# ServoBoard.net
KiCad netlist of a schematic drawn in Altium Designer
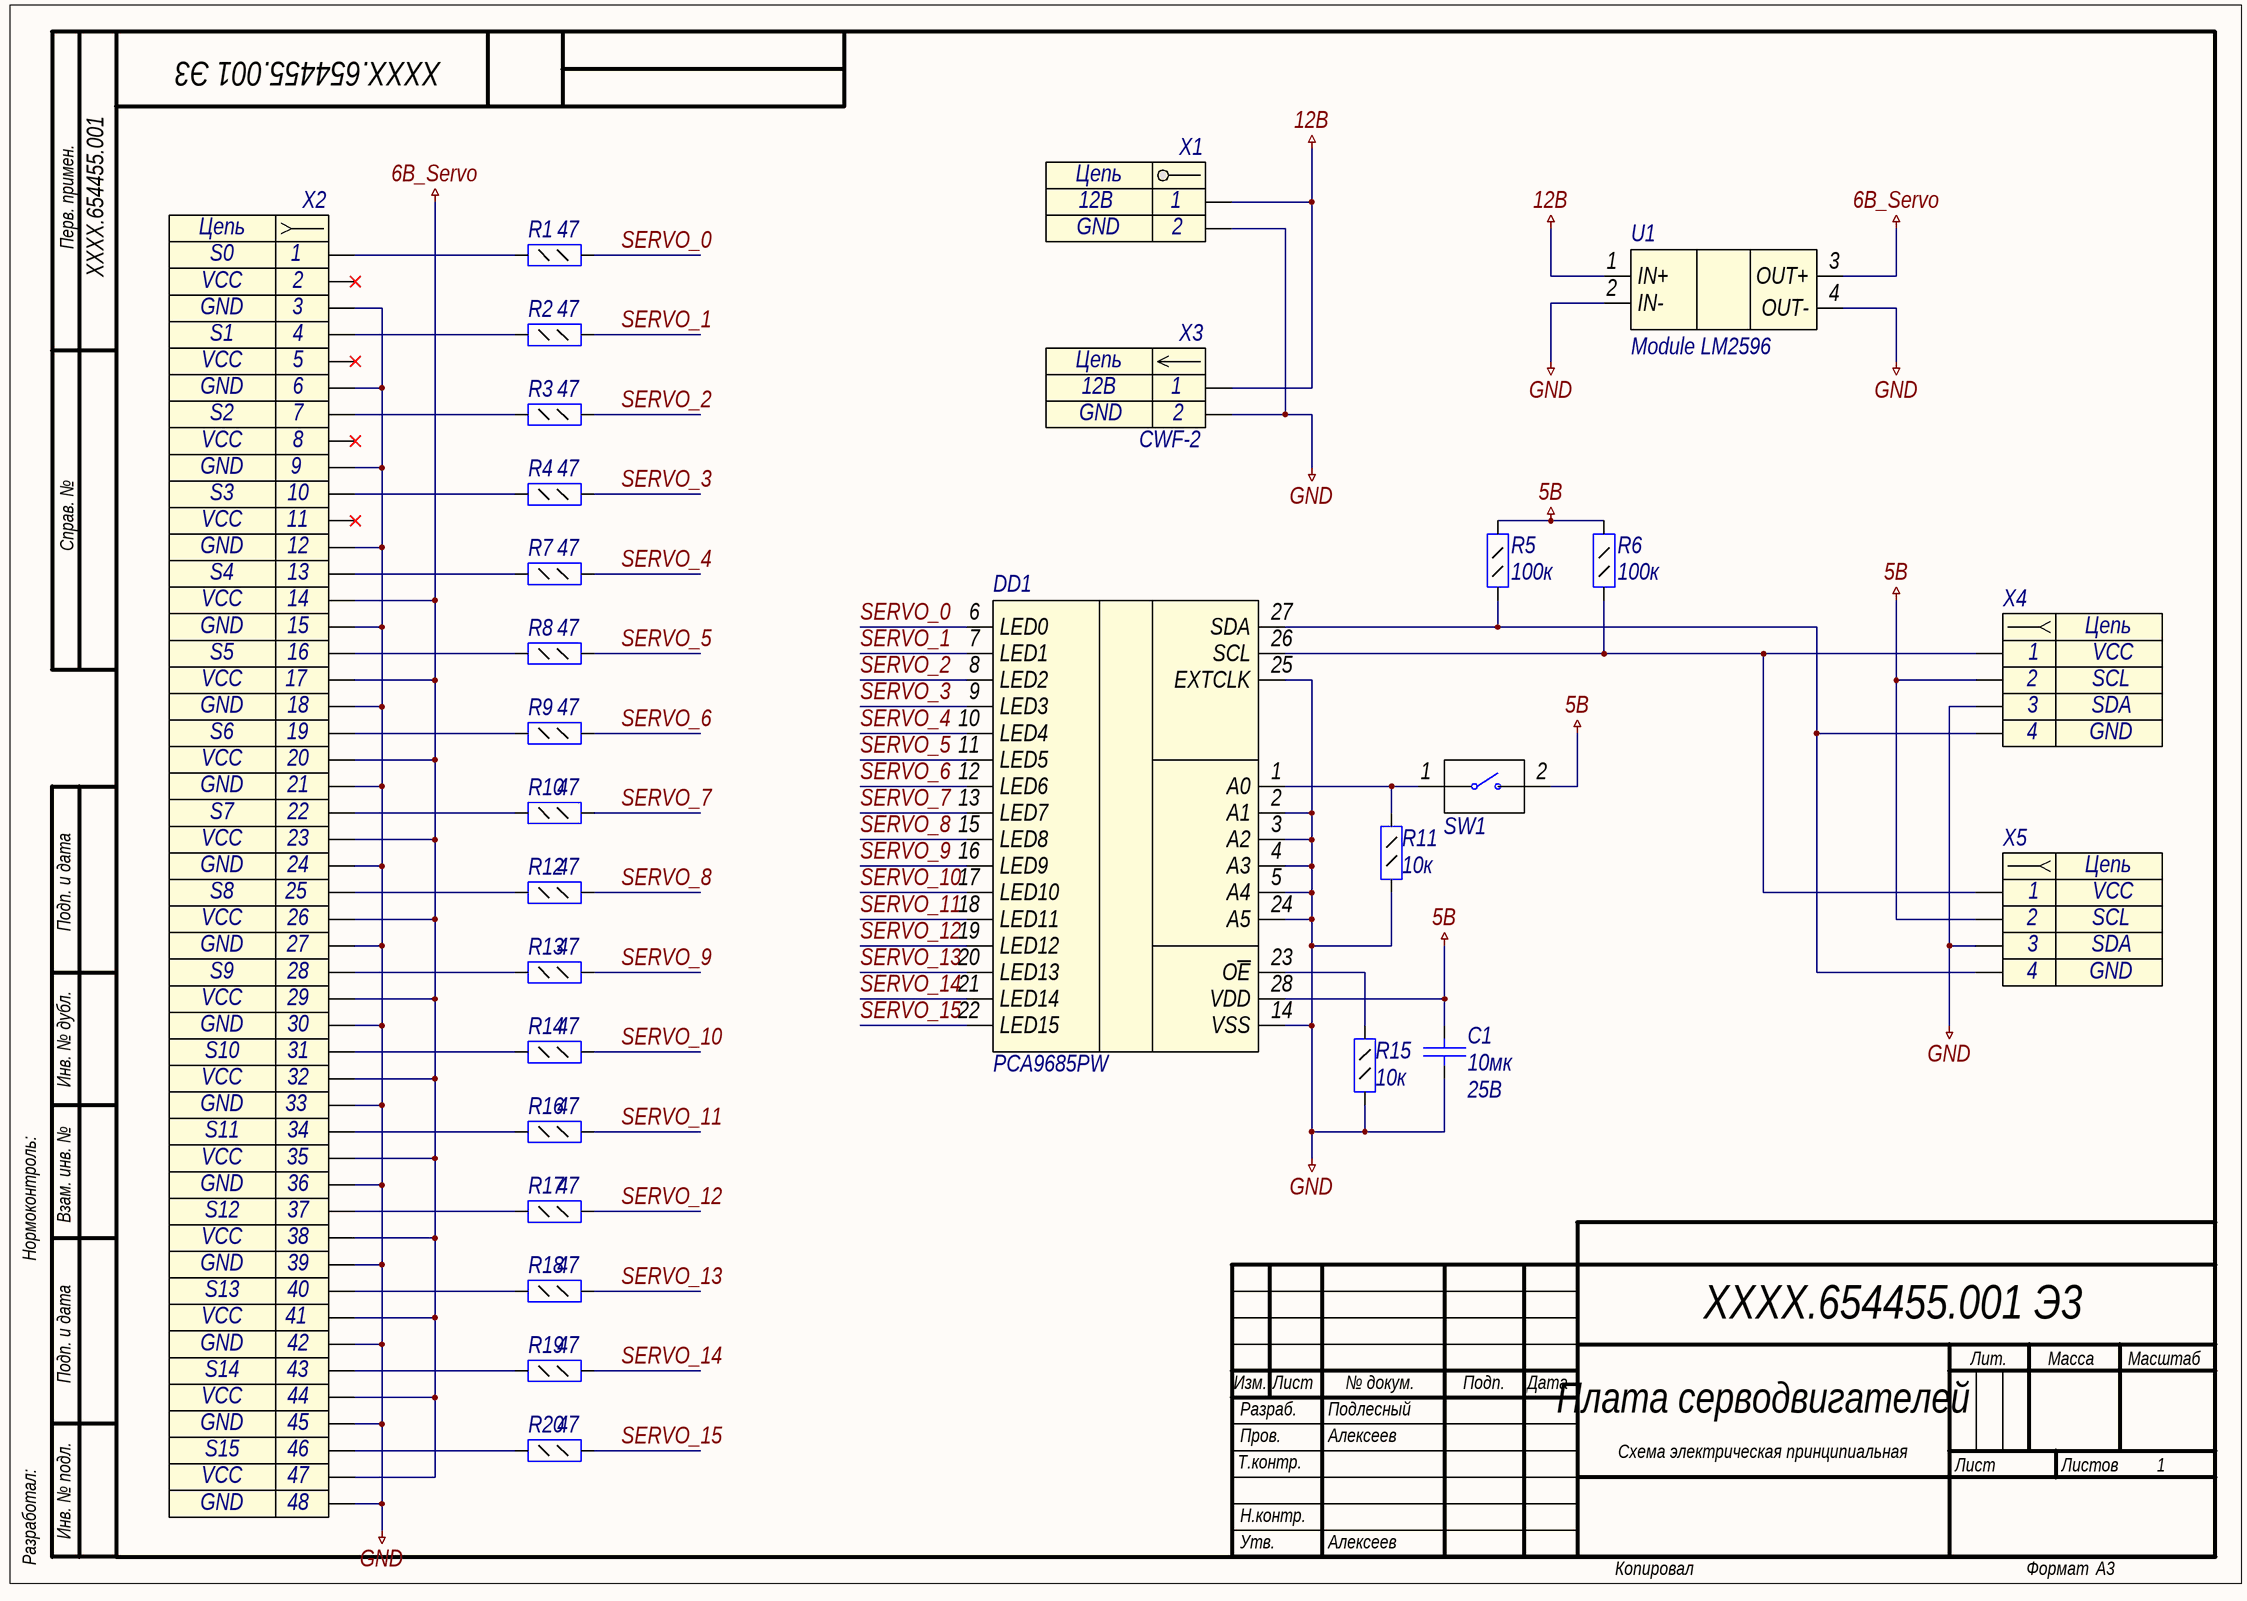
[diagram p0: ServoBoard.schdoc]

(export (version "E")
  (design (tool "Eeschema 10.0.6"))
  (components
    (comp (ref "C1")
      (value "10мк")
      (footprint "C1206")
      (description "Конденсатор")
      (fields
        (field (name "VOLTAGE") "25В")
        (field (name "PART NUMBER") "GRM31CR71E106KA12L*")
        (field (name "Comment") "Capacitor")
      )
      (libsource (lib "MOP44") (part "Capacitor"))
    )
    (comp (ref "DD1")
      (value "PCA9685PW")
      (footprint "TSSOP28")
      (description "Драйвер светодиода, 16 выходов")
      (fields (field (name "PART NUMBER") "PCA9685PW,112"))
      (libsource (lib "MOP44") (part "PCA9685PW"))
    )
    (comp (ref "R1")
      (value "47")
      (footprint "R0805")
      (description "Резистор")
      (fields (field (name "PART NUMBER") "RC0805FR-0747RL") (field (name "POWER") "0,125Вт"))
      (libsource (lib "MOP44") (part "Resistor_0,125Вт"))
    )
    (comp (ref "R2")
      (value "47")
      (footprint "R0805")
      (description "Резистор")
      (fields (field (name "PART NUMBER") "RC0805FR-0747RL") (field (name "POWER") "0,125Вт"))
      (libsource (lib "MOP44") (part "Resistor_0,125Вт"))
    )
    (comp (ref "R3")
      (value "47")
      (footprint "R0805")
      (description "Резистор")
      (fields (field (name "PART NUMBER") "RC0805FR-0747RL") (field (name "POWER") "0,125Вт"))
      (libsource (lib "MOP44") (part "Resistor_0,125Вт"))
    )
    (comp (ref "R4")
      (value "47")
      (footprint "R0805")
      (description "Резистор")
      (fields (field (name "PART NUMBER") "RC0805FR-0747RL") (field (name "POWER") "0,125Вт"))
      (libsource (lib "MOP44") (part "Resistor_0,125Вт"))
    )
    (comp (ref "R5")
      (value "100к")
      (footprint "R0805")
      (description "Резистор")
      (fields (field (name "PART NUMBER") "RC0805FR-07100KL") (field (name "POWER") "0,125Вт"))
      (libsource (lib "") (part "Resistor_0,125Вт_1"))
    )
    (comp (ref "R6")
      (value "100к")
      (footprint "R0805")
      (description "Резистор")
      (fields (field (name "PART NUMBER") "RC0805FR-07100KL") (field (name "POWER") "0,125Вт"))
      (libsource (lib "") (part "Resistor_0,125Вт_1"))
    )
    (comp (ref "R7")
      (value "47")
      (footprint "R0805")
      (description "Резистор")
      (fields (field (name "PART NUMBER") "RC0805FR-0747RL") (field (name "POWER") "0,125Вт"))
      (libsource (lib "MOP44") (part "Resistor_0,125Вт"))
    )
    (comp (ref "R8")
      (value "47")
      (footprint "R0805")
      (description "Резистор")
      (fields (field (name "PART NUMBER") "RC0805FR-0747RL") (field (name "POWER") "0,125Вт"))
      (libsource (lib "MOP44") (part "Resistor_0,125Вт"))
    )
    (comp (ref "R9")
      (value "47")
      (footprint "R0805")
      (description "Резистор")
      (fields (field (name "PART NUMBER") "RC0805FR-0747RL") (field (name "POWER") "0,125Вт"))
      (libsource (lib "MOP44") (part "Resistor_0,125Вт"))
    )
    (comp (ref "R10")
      (value "47")
      (footprint "R0805")
      (description "Резистор")
      (fields (field (name "PART NUMBER") "RC0805FR-0747RL") (field (name "POWER") "0,125Вт"))
      (libsource (lib "MOP44") (part "Resistor_0,125Вт"))
    )
    (comp (ref "R11")
      (value "10к")
      (footprint "R0805")
      (description "Резистор")
      (fields (field (name "POWER") "0,125Вт") (field (name "Comment") "Resistor_0,125Вт"))
      (libsource (lib "") (part "Resistor_0,125Вт_2"))
    )
    (comp (ref "R12")
      (value "47")
      (footprint "R0805")
      (description "Резистор")
      (fields (field (name "PART NUMBER") "RC0805FR-0747RL") (field (name "POWER") "0,125Вт"))
      (libsource (lib "MOP44") (part "Resistor_0,125Вт"))
    )
    (comp (ref "R13")
      (value "47")
      (footprint "R0805")
      (description "Резистор")
      (fields (field (name "PART NUMBER") "RC0805FR-0747RL") (field (name "POWER") "0,125Вт"))
      (libsource (lib "MOP44") (part "Resistor_0,125Вт"))
    )
    (comp (ref "R14")
      (value "47")
      (footprint "R0805")
      (description "Резистор")
      (fields (field (name "PART NUMBER") "RC0805FR-0747RL") (field (name "POWER") "0,125Вт"))
      (libsource (lib "MOP44") (part "Resistor_0,125Вт"))
    )
    (comp (ref "R15")
      (value "10к")
      (footprint "R0805")
      (description "Резистор")
      (fields (field (name "POWER") "0,125Вт") (field (name "Comment") "Resistor_0,125Вт"))
      (libsource (lib "") (part "Resistor_0,125Вт_2"))
    )
    (comp (ref "R16")
      (value "47")
      (footprint "R0805")
      (description "Резистор")
      (fields (field (name "PART NUMBER") "RC0805FR-0747RL") (field (name "POWER") "0,125Вт"))
      (libsource (lib "MOP44") (part "Resistor_0,125Вт"))
    )
    (comp (ref "R17")
      (value "47")
      (footprint "R0805")
      (description "Резистор")
      (fields (field (name "PART NUMBER") "RC0805FR-0747RL") (field (name "POWER") "0,125Вт"))
      (libsource (lib "MOP44") (part "Resistor_0,125Вт"))
    )
    (comp (ref "R18")
      (value "47")
      (footprint "R0805")
      (description "Резистор")
      (fields (field (name "PART NUMBER") "RC0805FR-0747RL") (field (name "POWER") "0,125Вт"))
      (libsource (lib "MOP44") (part "Resistor_0,125Вт"))
    )
    (comp (ref "R19")
      (value "47")
      (footprint "R0805")
      (description "Резистор")
      (fields (field (name "PART NUMBER") "RC0805FR-0747RL") (field (name "POWER") "0,125Вт"))
      (libsource (lib "MOP44") (part "Resistor_0,125Вт"))
    )
    (comp (ref "R20")
      (value "47")
      (footprint "R0805")
      (description "Резистор")
      (fields (field (name "PART NUMBER") "RC0805FR-0747RL") (field (name "POWER") "0,125Вт"))
      (libsource (lib "MOP44") (part "Resistor_0,125Вт"))
    )
    (comp (ref "SW1")
      (value "DS1040-01")
      (footprint "1PAD_ADR")
      (description "DIP переключатель")
      (libsource (lib "MOP44") (part "DS1040-01"))
    )
    (comp (ref "U1")
      (value "Module LM2596")
      (footprint "module LM2596")
      (description "Low-Dropout Regulator for 5-V to 3.3-V Conversion")
      (libsource (lib "MOP44") (part "Module LM2596"))
    )
    (comp (ref "X1")
      (value "Header_2_trm")
      (footprint "TERMINAL-2WAY-3.5MM")
      (description "Разъем - 2 конт. клеммник")
      (libsource (lib "MOP44") (part "Header_2_trm"))
    )
    (comp (ref "X2")
      (value "Header_48_plg")
      (footprint "PLS-48")
      (description "Разъем - 5 конт. вилка")
      (fields (field (name "PART NUMBER") "DS1021-1*48SF112-B"))
      (libsource (lib "MOP44") (part "Header_48_plg"))
    )
    (comp (ref "X3")
      (value "~")
      (footprint "CWF-2")
      (description "Разъем - 2 конт. вилка")
      (fields (field (name "PART NAME") "CWF-2") (field (name "PART NUMBER") "DS1069-2MVW6X"))
      (libsource (lib "MOP44") (part "Header_2_plg"))
    )
    (comp (ref "X4")
      (value "Header_4_sct")
      (footprint "RJ11_4P4C_V")
      (description "Разъем - 4 конт. розетка")
      (libsource (lib "MOP44") (part "Header_4_sct"))
    )
    (comp (ref "X5")
      (value "Header_4_sct")
      (footprint "RJ11_4P4C_V")
      (description "Разъем - 4 конт. розетка")
      (libsource (lib "MOP44") (part "Header_4_sct"))
    )
  )
  (nets
    (net (code "1") (name "/SERVO_0") (class "Default")
      (node (ref "DD1") (pin "6") (pinfunction "LED0_6") (pintype "power_in"))
      (node (ref "R1") (pin "2") (pinfunction "2_2") (pintype "passive"))
    )
    (net (code "2") (name "/SERVO_1") (class "Default")
      (node (ref "DD1") (pin "7") (pinfunction "LED1_7") (pintype "power_in"))
      (node (ref "R2") (pin "2") (pinfunction "2_2") (pintype "passive"))
    )
    (net (code "3") (name "/SERVO_2") (class "Default")
      (node (ref "DD1") (pin "8") (pinfunction "LED2_8") (pintype "power_in"))
      (node (ref "R3") (pin "2") (pinfunction "2_2") (pintype "passive"))
    )
    (net (code "4") (name "/SERVO_3") (class "Default")
      (node (ref "DD1") (pin "9") (pinfunction "LED3_9") (pintype "power_in"))
      (node (ref "R4") (pin "2") (pinfunction "2_2") (pintype "passive"))
    )
    (net (code "5") (name "/SERVO_4") (class "Default")
      (node (ref "DD1") (pin "10") (pinfunction "LED4_10") (pintype "power_in"))
      (node (ref "R7") (pin "2") (pinfunction "2_2") (pintype "passive"))
    )
    (net (code "6") (name "/SERVO_5") (class "Default")
      (node (ref "DD1") (pin "11") (pinfunction "LED5_11") (pintype "power_in"))
      (node (ref "R8") (pin "2") (pinfunction "2_2") (pintype "passive"))
    )
    (net (code "7") (name "/SERVO_6") (class "Default")
      (node (ref "DD1") (pin "12") (pinfunction "LED6_12") (pintype "power_in"))
      (node (ref "R9") (pin "2") (pinfunction "2_2") (pintype "passive"))
    )
    (net (code "8") (name "/SERVO_7") (class "Default")
      (node (ref "DD1") (pin "13") (pinfunction "LED7_13") (pintype "power_in"))
      (node (ref "R10") (pin "2") (pinfunction "2_2") (pintype "passive"))
    )
    (net (code "9") (name "/SERVO_8") (class "Default")
      (node (ref "DD1") (pin "15") (pinfunction "LED8_15") (pintype "power_in"))
      (node (ref "R12") (pin "2") (pinfunction "2_2") (pintype "passive"))
    )
    (net (code "10") (name "/SERVO_9") (class "Default")
      (node (ref "DD1") (pin "16") (pinfunction "LED9_16") (pintype "power_in"))
      (node (ref "R13") (pin "2") (pinfunction "2_2") (pintype "passive"))
    )
    (net (code "11") (name "/SERVO_10") (class "Default")
      (node (ref "DD1") (pin "17") (pinfunction "LED10_17") (pintype "power_in"))
      (node (ref "R14") (pin "2") (pinfunction "2_2") (pintype "passive"))
    )
    (net (code "12") (name "/SERVO_11") (class "Default")
      (node (ref "DD1") (pin "18") (pinfunction "LED11_18") (pintype "power_in"))
      (node (ref "R16") (pin "2") (pinfunction "2_2") (pintype "passive"))
    )
    (net (code "13") (name "/SERVO_12") (class "Default")
      (node (ref "DD1") (pin "19") (pinfunction "LED12_19") (pintype "power_in"))
      (node (ref "R17") (pin "2") (pinfunction "2_2") (pintype "passive"))
    )
    (net (code "14") (name "/SERVO_13") (class "Default")
      (node (ref "DD1") (pin "20") (pinfunction "LED13_20") (pintype "power_in"))
      (node (ref "R18") (pin "2") (pinfunction "2_2") (pintype "passive"))
    )
    (net (code "15") (name "/SERVO_14") (class "Default")
      (node (ref "DD1") (pin "21") (pinfunction "LED14_21") (pintype "power_in"))
      (node (ref "R19") (pin "2") (pinfunction "2_2") (pintype "passive"))
    )
    (net (code "16") (name "/SERVO_15") (class "Default")
      (node (ref "DD1") (pin "22") (pinfunction "LED15_22") (pintype "power_in"))
      (node (ref "R20") (pin "2") (pinfunction "2_2") (pintype "passive"))
    )
    (net (code "17") (name "5B") (class "Default")
      (node (ref "C1") (pin "2") (pinfunction "2_2") (pintype "passive"))
      (node (ref "DD1") (pin "28") (pinfunction "VDD_28") (pintype "power_in"))
      (node (ref "R5") (pin "2") (pinfunction "2_2") (pintype "passive"))
      (node (ref "R6") (pin "2") (pinfunction "2_2") (pintype "passive"))
      (node (ref "SW1") (pin "2") (pintype "passive"))
      (node (ref "X4") (pin "2") (pinfunction "2_2") (pintype "passive"))
      (node (ref "X5") (pin "2") (pinfunction "2_2") (pintype "passive"))
    )
    (net (code "18") (name "6B_Servo") (class "Default")
      (node (ref "U1") (pin "3") (pinfunction "OUT+_3") (pintype "power_in"))
      (node (ref "X2") (pin "14") (pinfunction "14_14") (pintype "passive"))
      (node (ref "X2") (pin "17") (pinfunction "17_17") (pintype "passive"))
      (node (ref "X2") (pin "20") (pinfunction "20_20") (pintype "passive"))
      (node (ref "X2") (pin "23") (pinfunction "23_23") (pintype "passive"))
      (node (ref "X2") (pin "26") (pinfunction "26_26") (pintype "passive"))
      (node (ref "X2") (pin "29") (pinfunction "29_29") (pintype "passive"))
      (node (ref "X2") (pin "32") (pinfunction "32_32") (pintype "passive"))
      (node (ref "X2") (pin "35") (pinfunction "35_35") (pintype "passive"))
      (node (ref "X2") (pin "38") (pinfunction "38_38") (pintype "passive"))
      (node (ref "X2") (pin "41") (pinfunction "41_41") (pintype "passive"))
      (node (ref "X2") (pin "44") (pinfunction "44_44") (pintype "passive"))
      (node (ref "X2") (pin "47") (pinfunction "47_47") (pintype "passive"))
    )
    (net (code "19") (name "12B") (class "Default")
      (node (ref "U1") (pin "1") (pinfunction "IN+_1") (pintype "power_in"))
      (node (ref "X1") (pin "1") (pinfunction "1_1") (pintype "passive"))
      (node (ref "X3") (pin "1") (pinfunction "1_1") (pintype "passive"))
    )
    (net (code "20") (name "GND") (class "Default")
      (node (ref "C1") (pin "1") (pinfunction "1_1") (pintype "passive"))
      (node (ref "DD1") (pin "14") (pinfunction "VSS_14") (pintype "power_in"))
      (node (ref "DD1") (pin "2") (pinfunction "A1_2") (pintype "power_in"))
      (node (ref "DD1") (pin "24") (pinfunction "A5_24") (pintype "power_in"))
      (node (ref "DD1") (pin "25") (pinfunction "EXTCLK_25") (pintype "power_in"))
      (node (ref "DD1") (pin "3") (pinfunction "A2_3") (pintype "power_in"))
      (node (ref "DD1") (pin "4") (pinfunction "A3_4") (pintype "power_in"))
      (node (ref "DD1") (pin "5") (pinfunction "A4_5") (pintype "power_in"))
      (node (ref "R11") (pin "2") (pinfunction "2_2") (pintype "passive"))
      (node (ref "R15") (pin "2") (pinfunction "2_2") (pintype "passive"))
      (node (ref "U1") (pin "2") (pinfunction "IN-_2") (pintype "power_in"))
      (node (ref "U1") (pin "4") (pinfunction "OUT-_4") (pintype "power_in"))
      (node (ref "X1") (pin "2") (pinfunction "2_2") (pintype "passive"))
      (node (ref "X2") (pin "12") (pinfunction "12_12") (pintype "passive"))
      (node (ref "X2") (pin "15") (pinfunction "15_15") (pintype "passive"))
      (node (ref "X2") (pin "18") (pinfunction "18_18") (pintype "passive"))
      (node (ref "X2") (pin "21") (pinfunction "21_21") (pintype "passive"))
      (node (ref "X2") (pin "24") (pinfunction "24_24") (pintype "passive"))
      (node (ref "X2") (pin "27") (pinfunction "27_27") (pintype "passive"))
      (node (ref "X2") (pin "3") (pinfunction "3_3") (pintype "passive"))
      (node (ref "X2") (pin "30") (pinfunction "30_30") (pintype "passive"))
      (node (ref "X2") (pin "33") (pinfunction "33_33") (pintype "passive"))
      (node (ref "X2") (pin "36") (pinfunction "36_36") (pintype "passive"))
      (node (ref "X2") (pin "39") (pinfunction "39_39") (pintype "passive"))
      (node (ref "X2") (pin "42") (pinfunction "42_42") (pintype "passive"))
      (node (ref "X2") (pin "45") (pinfunction "45_45") (pintype "passive"))
      (node (ref "X2") (pin "48") (pinfunction "48_48") (pintype "passive"))
      (node (ref "X2") (pin "6") (pinfunction "6_6") (pintype "passive"))
      (node (ref "X2") (pin "9") (pinfunction "9_9") (pintype "passive"))
      (node (ref "X3") (pin "2") (pinfunction "2_2") (pintype "passive"))
      (node (ref "X4") (pin "3") (pinfunction "3_3") (pintype "passive"))
      (node (ref "X5") (pin "3") (pinfunction "3_3") (pintype "passive"))
    )
    (net (code "21") (name "Net-(DD1-A0)") (class "Default")
      (node (ref "DD1") (pin "1") (pinfunction "A0_1") (pintype "power_in"))
      (node (ref "R11") (pin "1") (pinfunction "1_1") (pintype "passive"))
      (node (ref "SW1") (pin "1") (pintype "passive"))
    )
    (net (code "22") (name "Net-(DD1-O~{E})") (class "Default")
      (node (ref "DD1") (pin "23") (pinfunction "O~{E}_23") (pintype "power_in"))
      (node (ref "R15") (pin "1") (pinfunction "1_1") (pintype "passive"))
    )
    (net (code "23") (name "Net-(DD1-SCL)") (class "Default")
      (node (ref "DD1") (pin "26") (pinfunction "SCL_26") (pintype "power_in"))
      (node (ref "R6") (pin "1") (pinfunction "1_1") (pintype "passive"))
      (node (ref "X4") (pin "1") (pinfunction "1_1") (pintype "passive"))
      (node (ref "X5") (pin "1") (pinfunction "1_1") (pintype "passive"))
    )
    (net (code "24") (name "Net-(DD1-SDA)") (class "Default")
      (node (ref "DD1") (pin "27") (pinfunction "SDA_27") (pintype "power_in"))
      (node (ref "R5") (pin "1") (pinfunction "1_1") (pintype "passive"))
      (node (ref "X4") (pin "4") (pinfunction "4_4") (pintype "passive"))
      (node (ref "X5") (pin "4") (pinfunction "4_4") (pintype "passive"))
    )
    (net (code "25") (name "Net-(R1-Pad1)") (class "Default")
      (node (ref "R1") (pin "1") (pinfunction "1_1") (pintype "passive"))
      (node (ref "X2") (pin "1") (pinfunction "1_1") (pintype "passive"))
    )
    (net (code "26") (name "Net-(R2-Pad1)") (class "Default")
      (node (ref "R2") (pin "1") (pinfunction "1_1") (pintype "passive"))
      (node (ref "X2") (pin "4") (pinfunction "4_4") (pintype "passive"))
    )
    (net (code "27") (name "Net-(R3-Pad1)") (class "Default")
      (node (ref "R3") (pin "1") (pinfunction "1_1") (pintype "passive"))
      (node (ref "X2") (pin "7") (pinfunction "7_7") (pintype "passive"))
    )
    (net (code "28") (name "Net-(R4-Pad1)") (class "Default")
      (node (ref "R4") (pin "1") (pinfunction "1_1") (pintype "passive"))
      (node (ref "X2") (pin "10") (pinfunction "10_10") (pintype "passive"))
    )
    (net (code "29") (name "Net-(R7-Pad1)") (class "Default")
      (node (ref "R7") (pin "1") (pinfunction "1_1") (pintype "passive"))
      (node (ref "X2") (pin "13") (pinfunction "13_13") (pintype "passive"))
    )
    (net (code "30") (name "Net-(R8-Pad1)") (class "Default")
      (node (ref "R8") (pin "1") (pinfunction "1_1") (pintype "passive"))
      (node (ref "X2") (pin "16") (pinfunction "16_16") (pintype "passive"))
    )
    (net (code "31") (name "Net-(R9-Pad1)") (class "Default")
      (node (ref "R9") (pin "1") (pinfunction "1_1") (pintype "passive"))
      (node (ref "X2") (pin "19") (pinfunction "19_19") (pintype "passive"))
    )
    (net (code "32") (name "Net-(R10-Pad1)") (class "Default")
      (node (ref "R10") (pin "1") (pinfunction "1_1") (pintype "passive"))
      (node (ref "X2") (pin "22") (pinfunction "22_22") (pintype "passive"))
    )
    (net (code "33") (name "Net-(R12-Pad1)") (class "Default")
      (node (ref "R12") (pin "1") (pinfunction "1_1") (pintype "passive"))
      (node (ref "X2") (pin "25") (pinfunction "25_25") (pintype "passive"))
    )
    (net (code "34") (name "Net-(R13-Pad1)") (class "Default")
      (node (ref "R13") (pin "1") (pinfunction "1_1") (pintype "passive"))
      (node (ref "X2") (pin "28") (pinfunction "28_28") (pintype "passive"))
    )
    (net (code "35") (name "Net-(R14-Pad1)") (class "Default")
      (node (ref "R14") (pin "1") (pinfunction "1_1") (pintype "passive"))
      (node (ref "X2") (pin "31") (pinfunction "31_31") (pintype "passive"))
    )
    (net (code "36") (name "Net-(R16-Pad1)") (class "Default")
      (node (ref "R16") (pin "1") (pinfunction "1_1") (pintype "passive"))
      (node (ref "X2") (pin "34") (pinfunction "34_34") (pintype "passive"))
    )
    (net (code "37") (name "Net-(R17-Pad1)") (class "Default")
      (node (ref "R17") (pin "1") (pinfunction "1_1") (pintype "passive"))
      (node (ref "X2") (pin "37") (pinfunction "37_37") (pintype "passive"))
    )
    (net (code "38") (name "Net-(R18-Pad1)") (class "Default")
      (node (ref "R18") (pin "1") (pinfunction "1_1") (pintype "passive"))
      (node (ref "X2") (pin "40") (pinfunction "40_40") (pintype "passive"))
    )
    (net (code "39") (name "Net-(R19-Pad1)") (class "Default")
      (node (ref "R19") (pin "1") (pinfunction "1_1") (pintype "passive"))
      (node (ref "X2") (pin "43") (pinfunction "43_43") (pintype "passive"))
    )
    (net (code "40") (name "Net-(R20-Pad1)") (class "Default")
      (node (ref "R20") (pin "1") (pinfunction "1_1") (pintype "passive"))
      (node (ref "X2") (pin "46") (pinfunction "46_46") (pintype "passive"))
    )
    (net (code "41") (name "unconnected-(X2-Pad2)") (class "Default")
      (node (ref "X2") (pin "2") (pinfunction "2_2") (pintype "passive+no_connect"))
    )
    (net (code "42") (name "unconnected-(X2-Pad5)") (class "Default")
      (node (ref "X2") (pin "5") (pinfunction "5_5") (pintype "passive+no_connect"))
    )
    (net (code "43") (name "unconnected-(X2-Pad8)") (class "Default")
      (node (ref "X2") (pin "8") (pinfunction "8_8") (pintype "passive+no_connect"))
    )
    (net (code "44") (name "unconnected-(X2-Pad11)") (class "Default")
      (node (ref "X2") (pin "11") (pinfunction "11_11") (pintype "passive+no_connect"))
    )
  )
)
